# semafor-a.net
KiCad netlist of a schematic drawn in EAGLE
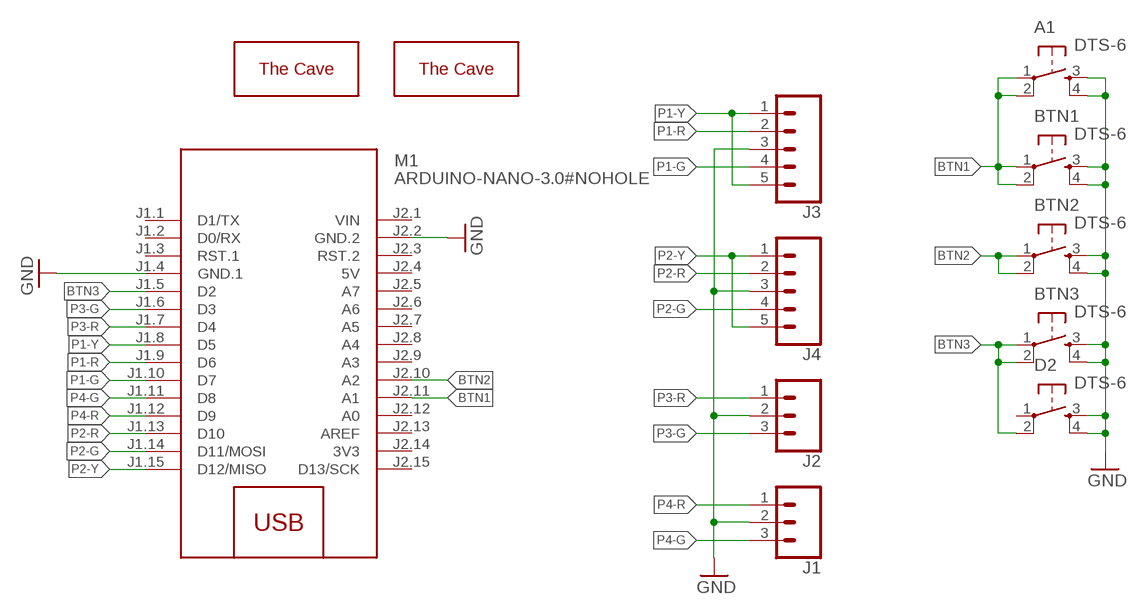
[diagram p0: schematic, sheet 1]

(export (version "E")
  (design (tool "Eeschema 10.0.6"))
  (components
    (comp (ref "A1")
      (value "DTS-6")
      (footprint "eagle-import:DTS-6")
      (libsource (lib "eagle-import") (part "DTS-6"))
    )
    (comp (ref "BTN1")
      (value "DTS-6")
      (footprint "eagle-import:DTS-6")
      (libsource (lib "eagle-import") (part "DTS-6"))
    )
    (comp (ref "BTN2")
      (value "DTS-6")
      (footprint "eagle-import:DTS-6")
      (libsource (lib "eagle-import") (part "DTS-6"))
    )
    (comp (ref "BTN3")
      (value "DTS-6")
      (footprint "eagle-import:DTS-6")
      (libsource (lib "eagle-import") (part "DTS-6"))
    )
    (comp (ref "D2")
      (value "DTS-6")
      (footprint "eagle-import:DTS-6")
      (libsource (lib "eagle-import") (part "DTS-6"))
    )
    (comp (ref "J1")
      (value "CONN_031X03_NO_SILK")
      (footprint "eagle-import:1X03_NO_SILK")
      (libsource (lib "eagle-import") (part "CONN_031X03_NO_SILK"))
    )
    (comp (ref "J2")
      (value "CONN_031X03_NO_SILK")
      (footprint "eagle-import:1X03_NO_SILK")
      (libsource (lib "eagle-import") (part "CONN_031X03_NO_SILK"))
    )
    (comp (ref "J3")
      (value "CONN_05NO_SILK")
      (footprint "eagle-import:1X05_NO_SILK")
      (libsource (lib "eagle-import") (part "CONN_05NO_SILK"))
    )
    (comp (ref "J4")
      (value "CONN_05NO_SILK")
      (footprint "eagle-import:1X05_NO_SILK")
      (libsource (lib "eagle-import") (part "CONN_05NO_SILK"))
    )
    (comp (ref "M1")
      (value "ARDUINO-NANO-3.0#NOHOLE")
      (footprint "eagle-import:ARDUINO-NANO-3.0")
      (libsource (lib "eagle-import") (part "ARDUINO-NANO-3.0#NOHOLE"))
    )
    (comp (ref "U$1")
      (value "THECAVE_LOGO_NEW_TOP_SMALL")
      (footprint "eagle-import:NEW_LOGO_SMALL_TOP")
      (libsource (lib "eagle-import") (part "THECAVE_LOGO_NEW_TOP_SMALL"))
    )
    (comp (ref "U$2")
      (value "THECAVE_LOGO_NEW_BOTTOM")
      (footprint "eagle-import:NEW_LOGO_BOTTOM")
      (libsource (lib "eagle-import") (part "THECAVE_LOGO_NEW_BOTTOM"))
    )
  )
  (nets
    (net (code "1") (name "/3V3") (class "Default")
      (node (ref "M1") (pin "J2.14") (pinfunction "3V3_J2.14") (pintype "power_in"))
    )
    (net (code "2") (name "/5V") (class "Default")
      (node (ref "M1") (pin "J2.4") (pinfunction "5V_J2.4") (pintype "power_in"))
    )
    (net (code "3") (name "/VIN") (class "Default")
      (node (ref "M1") (pin "J2.1") (pinfunction "VIN_J2.1") (pintype "power_in"))
    )
    (net (code "4") (name "BTN1") (class "Default")
      (node (ref "A1") (pin "1") (pinfunction "1_1") (pintype "passive"))
      (node (ref "A1") (pin "2") (pinfunction "2_2") (pintype "passive"))
      (node (ref "BTN1") (pin "1") (pinfunction "1_1") (pintype "passive"))
      (node (ref "BTN1") (pin "2") (pinfunction "2_2") (pintype "passive"))
      (node (ref "M1") (pin "J2.11") (pinfunction "A1_J2.11") (pintype "bidirectional"))
    )
    (net (code "5") (name "BTN2") (class "Default")
      (node (ref "BTN2") (pin "1") (pinfunction "1_1") (pintype "passive"))
      (node (ref "BTN2") (pin "2") (pinfunction "2_2") (pintype "passive"))
      (node (ref "M1") (pin "J2.10") (pinfunction "A2_J2.10") (pintype "bidirectional"))
    )
    (net (code "6") (name "BTN3") (class "Default")
      (node (ref "BTN3") (pin "1") (pinfunction "1_1") (pintype "passive"))
      (node (ref "BTN3") (pin "2") (pinfunction "2_2") (pintype "passive"))
      (node (ref "D2") (pin "2") (pinfunction "2_2") (pintype "passive"))
      (node (ref "M1") (pin "J1.5") (pinfunction "D2_J1.5") (pintype "bidirectional"))
    )
    (net (code "7") (name "GND") (class "Default")
      (node (ref "A1") (pin "3") (pinfunction "3_3") (pintype "passive"))
      (node (ref "A1") (pin "4") (pinfunction "4_4") (pintype "passive"))
      (node (ref "BTN1") (pin "3") (pinfunction "3_3") (pintype "passive"))
      (node (ref "BTN1") (pin "4") (pinfunction "4_4") (pintype "passive"))
      (node (ref "BTN2") (pin "3") (pinfunction "3_3") (pintype "passive"))
      (node (ref "BTN2") (pin "4") (pinfunction "4_4") (pintype "passive"))
      (node (ref "BTN3") (pin "3") (pinfunction "3_3") (pintype "passive"))
      (node (ref "BTN3") (pin "4") (pinfunction "4_4") (pintype "passive"))
      (node (ref "D2") (pin "3") (pinfunction "3_3") (pintype "passive"))
      (node (ref "D2") (pin "4") (pinfunction "4_4") (pintype "passive"))
      (node (ref "J1") (pin "2") (pinfunction "2_2") (pintype "passive"))
      (node (ref "J2") (pin "2") (pinfunction "2_2") (pintype "passive"))
      (node (ref "J3") (pin "3") (pinfunction "3_3") (pintype "passive"))
      (node (ref "J4") (pin "3") (pinfunction "3_3") (pintype "passive"))
      (node (ref "M1") (pin "J1.4") (pinfunction "GND.1_J1.4") (pintype "power_in"))
      (node (ref "M1") (pin "J2.2") (pinfunction "GND.2_J2.2") (pintype "power_in"))
    )
    (net (code "8") (name "P1-G") (class "Default")
      (node (ref "J3") (pin "4") (pinfunction "4_4") (pintype "passive"))
      (node (ref "M1") (pin "J1.10") (pinfunction "D7_J1.10") (pintype "bidirectional"))
    )
    (net (code "9") (name "P1-R") (class "Default")
      (node (ref "J3") (pin "2") (pinfunction "2_2") (pintype "passive"))
      (node (ref "M1") (pin "J1.9") (pinfunction "D6_J1.9") (pintype "bidirectional"))
    )
    (net (code "10") (name "P1-Y") (class "Default")
      (node (ref "J3") (pin "1") (pinfunction "1_1") (pintype "passive"))
      (node (ref "J3") (pin "5") (pinfunction "5_5") (pintype "passive"))
      (node (ref "M1") (pin "J1.8") (pinfunction "D5_J1.8") (pintype "bidirectional"))
    )
    (net (code "11") (name "P2-G") (class "Default")
      (node (ref "J4") (pin "4") (pinfunction "4_4") (pintype "passive"))
      (node (ref "M1") (pin "J1.14") (pinfunction "D11/MOSI_J1.14") (pintype "bidirectional"))
    )
    (net (code "12") (name "P2-R") (class "Default")
      (node (ref "J4") (pin "2") (pinfunction "2_2") (pintype "passive"))
      (node (ref "M1") (pin "J1.13") (pinfunction "D10_J1.13") (pintype "bidirectional"))
    )
    (net (code "13") (name "P2-Y") (class "Default")
      (node (ref "J4") (pin "1") (pinfunction "1_1") (pintype "passive"))
      (node (ref "J4") (pin "5") (pinfunction "5_5") (pintype "passive"))
      (node (ref "M1") (pin "J1.15") (pinfunction "D12/MISO_J1.15") (pintype "bidirectional"))
    )
    (net (code "14") (name "P3-G") (class "Default")
      (node (ref "J2") (pin "3") (pinfunction "3_3") (pintype "passive"))
      (node (ref "M1") (pin "J1.6") (pinfunction "D3_J1.6") (pintype "bidirectional"))
    )
    (net (code "15") (name "P3-R") (class "Default")
      (node (ref "J2") (pin "1") (pinfunction "1_1") (pintype "passive"))
      (node (ref "M1") (pin "J1.7") (pinfunction "D4_J1.7") (pintype "bidirectional"))
    )
    (net (code "16") (name "P4-G") (class "Default")
      (node (ref "J1") (pin "3") (pinfunction "3_3") (pintype "passive"))
      (node (ref "M1") (pin "J1.11") (pinfunction "D8_J1.11") (pintype "bidirectional"))
    )
    (net (code "17") (name "P4-R") (class "Default")
      (node (ref "J1") (pin "1") (pinfunction "1_1") (pintype "passive"))
      (node (ref "M1") (pin "J1.12") (pinfunction "D9_J1.12") (pintype "bidirectional"))
    )
    (net (code "18") (name "unconnected-(D2-Pad1)") (class "Default")
      (node (ref "D2") (pin "1") (pinfunction "1_1") (pintype "passive"))
    )
    (net (code "19") (name "unconnected-(M1-A0-PadJ2.12)") (class "Default")
      (node (ref "M1") (pin "J2.12") (pinfunction "A0_J2.12") (pintype "bidirectional"))
    )
    (net (code "20") (name "unconnected-(M1-A3-PadJ2.9)") (class "Default")
      (node (ref "M1") (pin "J2.9") (pinfunction "A3_J2.9") (pintype "bidirectional"))
    )
    (net (code "21") (name "unconnected-(M1-A4-PadJ2.8)") (class "Default")
      (node (ref "M1") (pin "J2.8") (pinfunction "A4_J2.8") (pintype "bidirectional"))
    )
    (net (code "22") (name "unconnected-(M1-A5-PadJ2.7)") (class "Default")
      (node (ref "M1") (pin "J2.7") (pinfunction "A5_J2.7") (pintype "bidirectional"))
    )
    (net (code "23") (name "unconnected-(M1-A6-PadJ2.6)") (class "Default")
      (node (ref "M1") (pin "J2.6") (pinfunction "A6_J2.6") (pintype "bidirectional"))
    )
    (net (code "24") (name "unconnected-(M1-A7-PadJ2.5)") (class "Default")
      (node (ref "M1") (pin "J2.5") (pinfunction "A7_J2.5") (pintype "bidirectional"))
    )
    (net (code "25") (name "unconnected-(M1-AREF-PadJ2.13)") (class "Default")
      (node (ref "M1") (pin "J2.13") (pinfunction "AREF_J2.13") (pintype "bidirectional"))
    )
    (net (code "26") (name "unconnected-(M1-D0{slash}RX-PadJ1.2)") (class "Default")
      (node (ref "M1") (pin "J1.2") (pinfunction "D0/RX_J1.2") (pintype "bidirectional"))
    )
    (net (code "27") (name "unconnected-(M1-D1{slash}TX-PadJ1.1)") (class "Default")
      (node (ref "M1") (pin "J1.1") (pinfunction "D1/TX_J1.1") (pintype "bidirectional"))
    )
    (net (code "28") (name "unconnected-(M1-D13{slash}SCK-PadJ2.15)") (class "Default")
      (node (ref "M1") (pin "J2.15") (pinfunction "D13/SCK_J2.15") (pintype "bidirectional"))
    )
    (net (code "29") (name "unconnected-(M1-RST.1-PadJ1.3)") (class "Default")
      (node (ref "M1") (pin "J1.3") (pinfunction "RST.1_J1.3") (pintype "bidirectional"))
    )
    (net (code "30") (name "unconnected-(M1-RST.2-PadJ2.3)") (class "Default")
      (node (ref "M1") (pin "J2.3") (pinfunction "RST.2_J2.3") (pintype "bidirectional"))
    )
  )
)
